# eps-v1-0.net
KiCad netlist of a schematic drawn in EAGLE
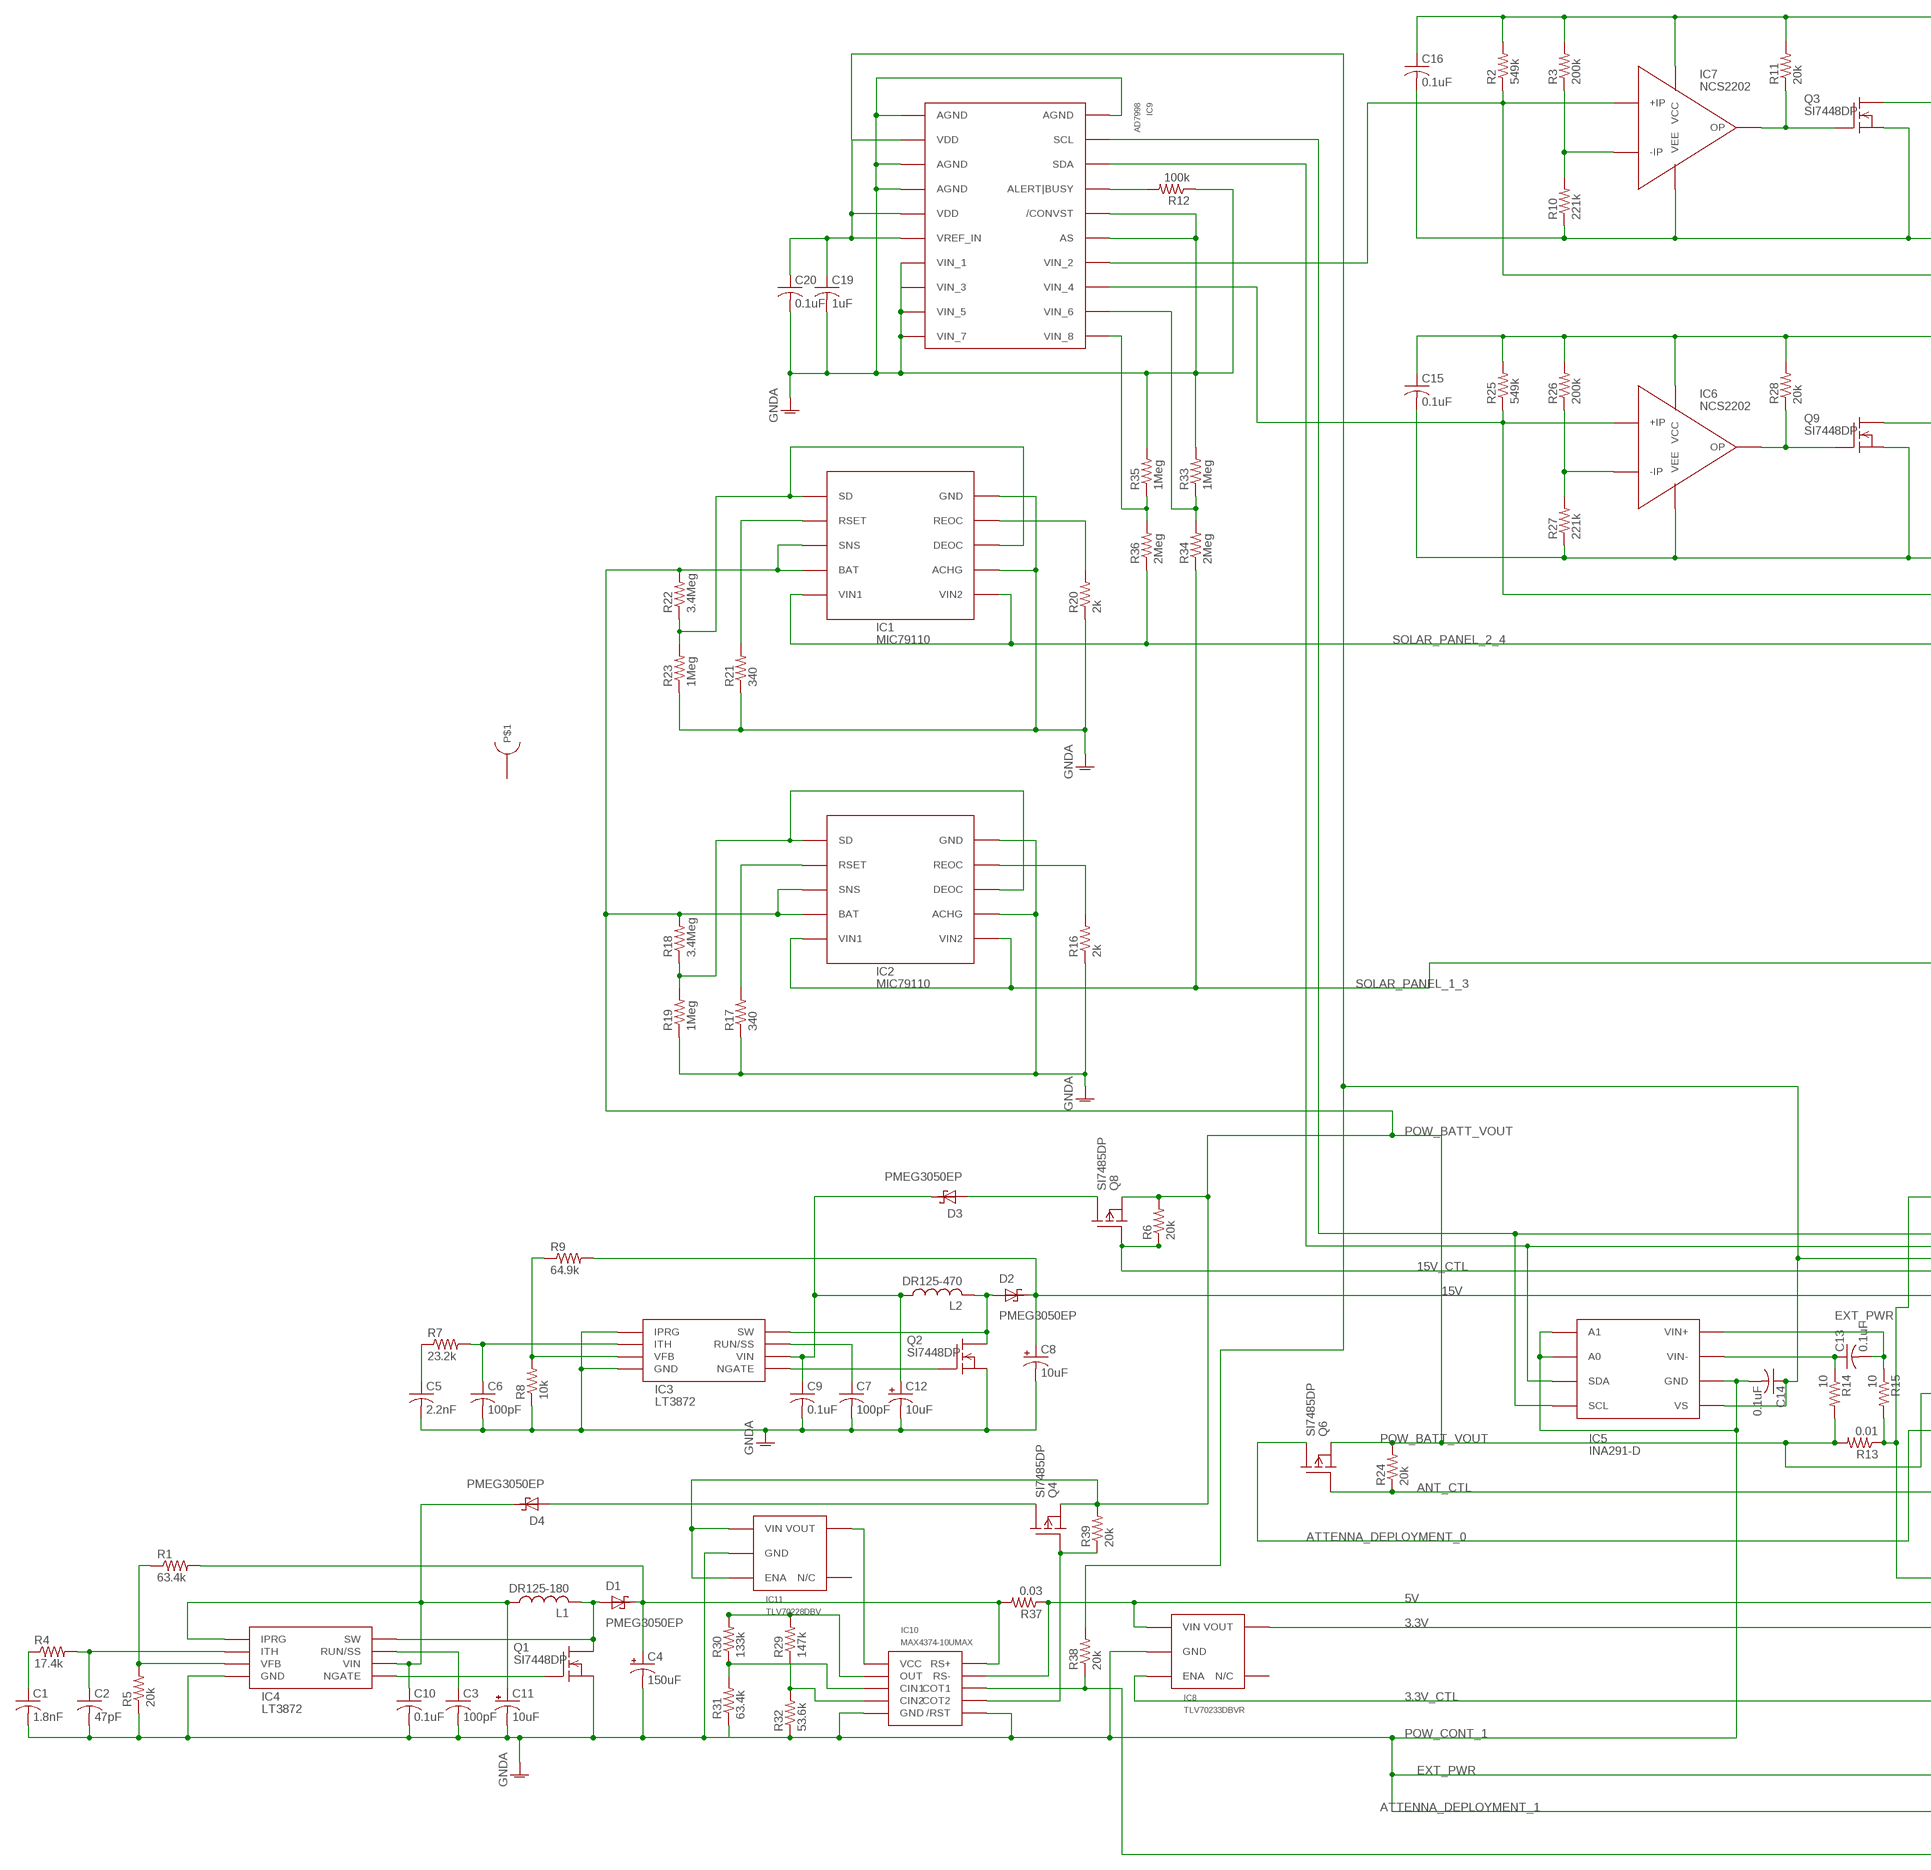
[diagram p0: schematic, sheet 1, part 1 of 2]
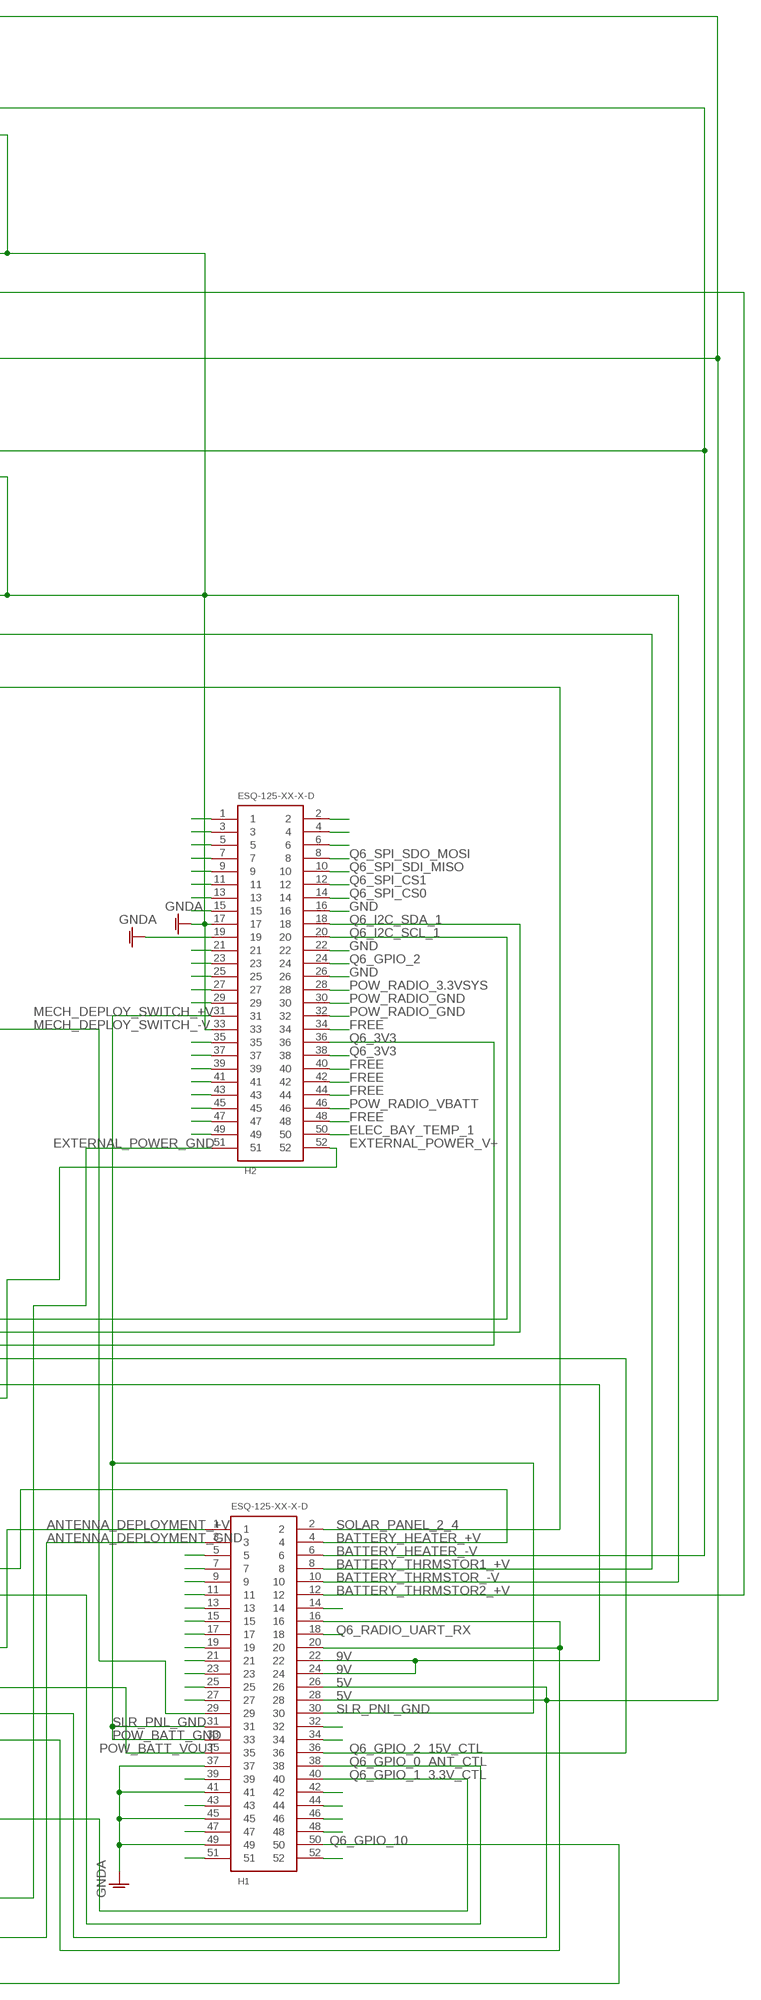
[diagram p1: schematic, sheet 1, part 2 of 2]

(export (version "E")
  (design (tool "Eeschema 10.0.6"))
  (components
    (comp (ref "C1")
      (value "1.8nF")
      (footprint "eagle-import:C0805")
      (libsource (lib "eagle-import") (part "C-USC0805"))
    )
    (comp (ref "C2")
      (value "47pF")
      (footprint "eagle-import:C0805")
      (libsource (lib "eagle-import") (part "C-USC0805"))
    )
    (comp (ref "C3")
      (value "100pF")
      (footprint "eagle-import:C0805")
      (libsource (lib "eagle-import") (part "C-USC0805"))
    )
    (comp (ref "C4")
      (value "150uF")
      (footprint "eagle-import:D_7343-31R")
      (libsource (lib "eagle-import") (part "CPOL-USD/7343-31R"))
    )
    (comp (ref "C5")
      (value "2.2nF")
      (footprint "eagle-import:C0805")
      (libsource (lib "eagle-import") (part "C-USC0805"))
    )
    (comp (ref "C6")
      (value "100pF")
      (footprint "eagle-import:C0805")
      (libsource (lib "eagle-import") (part "C-USC0805"))
    )
    (comp (ref "C7")
      (value "100pF")
      (footprint "eagle-import:C0805")
      (libsource (lib "eagle-import") (part "C-USC0805"))
    )
    (comp (ref "C8")
      (value "10uF")
      (footprint "eagle-import:D_7343-31R")
      (libsource (lib "eagle-import") (part "CPOL-USD/7343-31R"))
    )
    (comp (ref "C9")
      (value "0.1uF")
      (footprint "eagle-import:C0805")
      (libsource (lib "eagle-import") (part "C-USC0805"))
    )
    (comp (ref "C10")
      (value "0.1uF")
      (footprint "eagle-import:C0805")
      (libsource (lib "eagle-import") (part "C-USC0805"))
    )
    (comp (ref "C11")
      (value "10uF")
      (footprint "eagle-import:D_7343-31R")
      (libsource (lib "eagle-import") (part "CPOL-USD/7343-31R"))
    )
    (comp (ref "C12")
      (value "10uF")
      (footprint "eagle-import:D_7343-31R")
      (libsource (lib "eagle-import") (part "CPOL-USD/7343-31R"))
    )
    (comp (ref "C13")
      (value "0.1uF")
      (footprint "eagle-import:C0805")
      (libsource (lib "eagle-import") (part "C-USC0805"))
    )
    (comp (ref "C14")
      (value "0.1uF")
      (footprint "eagle-import:C0805")
      (libsource (lib "eagle-import") (part "C-USC0805"))
    )
    (comp (ref "C15")
      (value "0.1uF")
      (footprint "eagle-import:C0805")
      (libsource (lib "eagle-import") (part "C-USC0805"))
    )
    (comp (ref "C16")
      (value "0.1uF")
      (footprint "eagle-import:C0805")
      (libsource (lib "eagle-import") (part "C-USC0805"))
    )
    (comp (ref "C19")
      (value "1uF")
      (footprint "eagle-import:C0805")
      (libsource (lib "eagle-import") (part "C-USC0805"))
    )
    (comp (ref "C20")
      (value "0.1uF")
      (footprint "eagle-import:C0805")
      (libsource (lib "eagle-import") (part "C-USC0805"))
    )
    (comp (ref "D1")
      (value "PMEG3050EP")
      (footprint "eagle-import:SOD128")
      (libsource (lib "eagle-import") (part "PMEG3050EP"))
    )
    (comp (ref "D2")
      (value "PMEG3050EP")
      (footprint "eagle-import:SOD128")
      (libsource (lib "eagle-import") (part "PMEG3050EP"))
    )
    (comp (ref "D3")
      (value "PMEG3050EP")
      (footprint "eagle-import:SOD128")
      (libsource (lib "eagle-import") (part "PMEG3050EP"))
    )
    (comp (ref "D4")
      (value "PMEG3050EP")
      (footprint "eagle-import:SOD128")
      (libsource (lib "eagle-import") (part "PMEG3050EP"))
    )
    (comp (ref "H1")
      (value "ESQ-125-XX-X-D")
      (footprint "eagle-import:ESQ-125-XX-X-D")
      (libsource (lib "eagle-import") (part "ESQ-125-XX-X-D"))
    )
    (comp (ref "H2")
      (value "ESQ-125-XX-X-D")
      (footprint "eagle-import:ESQ-125-XX-X-D")
      (libsource (lib "eagle-import") (part "ESQ-125-XX-X-D"))
    )
    (comp (ref "IC1")
      (value "MIC79110")
      (footprint "eagle-import:MLF10-EP")
      (libsource (lib "eagle-import") (part "MIC79110"))
    )
    (comp (ref "IC2")
      (value "MIC79110")
      (footprint "eagle-import:MLF10-EP")
      (libsource (lib "eagle-import") (part "MIC79110"))
    )
    (comp (ref "IC3")
      (value "LT3872")
      (footprint "eagle-import:TSOT23-8")
      (libsource (lib "eagle-import") (part "LT3872"))
    )
    (comp (ref "IC4")
      (value "LT3872")
      (footprint "eagle-import:TSOT23-8")
      (libsource (lib "eagle-import") (part "LT3872"))
    )
    (comp (ref "IC5")
      (value "INA291-D")
      (footprint "eagle-import:SO08")
      (libsource (lib "eagle-import") (part "INA291-D"))
    )
    (comp (ref "IC6")
      (value "NCS2202")
      (footprint "eagle-import:SOT23-5")
      (libsource (lib "eagle-import") (part "NCS2202"))
    )
    (comp (ref "IC7")
      (value "NCS2202")
      (footprint "eagle-import:SOT23-5")
      (libsource (lib "eagle-import") (part "NCS2202"))
    )
    (comp (ref "IC8")
      (value "TLV70233DBVR")
      (footprint "eagle-import:SOT23-5")
      (libsource (lib "eagle-import") (part "TLV70233DBVR"))
    )
    (comp (ref "IC9")
      (value "AD7998")
      (footprint "eagle-import:TSSOP-20")
      (libsource (lib "eagle-import") (part "AD7998"))
    )
    (comp (ref "IC10")
      (value "MAX4374-10UMAX")
      (footprint "eagle-import:10UMAX")
      (libsource (lib "eagle-import") (part "MAX4374-10UMAX"))
    )
    (comp (ref "IC11")
      (value "TLV70228DBV")
      (footprint "eagle-import:SOT23-5")
      (libsource (lib "eagle-import") (part "TLV70228DBV"))
    )
    (comp (ref "L1")
      (value "DR125-180")
      (footprint "eagle-import:DR125")
      (libsource (lib "eagle-import") (part "DR125-180"))
    )
    (comp (ref "L2")
      (value "DR125-470")
      (footprint "eagle-import:DR125")
      (libsource (lib "eagle-import") (part "DR125-470"))
    )
    (comp (ref "Q1")
      (value "SI7448DP")
      (footprint "eagle-import:PPAK-SO08-EP")
      (libsource (lib "eagle-import") (part "SI7448DP"))
    )
    (comp (ref "Q2")
      (value "SI7448DP")
      (footprint "eagle-import:PPAK-SO08-EP")
      (libsource (lib "eagle-import") (part "SI7448DP"))
    )
    (comp (ref "Q3")
      (value "SI7448DP")
      (footprint "eagle-import:PPAK-SO08-EP")
      (libsource (lib "eagle-import") (part "SI7448DP"))
    )
    (comp (ref "Q4")
      (value "SI7485DP")
      (footprint "eagle-import:PPAK-SO08-EP")
      (libsource (lib "eagle-import") (part "SI7485DP"))
    )
    (comp (ref "Q6")
      (value "SI7485DP")
      (footprint "eagle-import:PPAK-SO08-EP")
      (libsource (lib "eagle-import") (part "SI7485DP"))
    )
    (comp (ref "Q8")
      (value "SI7485DP")
      (footprint "eagle-import:PPAK-SO08-EP")
      (libsource (lib "eagle-import") (part "SI7485DP"))
    )
    (comp (ref "Q9")
      (value "SI7448DP")
      (footprint "eagle-import:PPAK-SO08-EP")
      (libsource (lib "eagle-import") (part "SI7448DP"))
    )
    (comp (ref "R1")
      (value "63.4k")
      (footprint "eagle-import:M1206")
      (libsource (lib "eagle-import") (part "R-US_M1206"))
    )
    (comp (ref "R2")
      (value "549k")
      (footprint "eagle-import:M1206")
      (libsource (lib "eagle-import") (part "R-US_M1206"))
    )
    (comp (ref "R3")
      (value "200k")
      (footprint "eagle-import:M1206")
      (libsource (lib "eagle-import") (part "R-US_M1206"))
    )
    (comp (ref "R4")
      (value "17.4k")
      (footprint "eagle-import:M1206")
      (libsource (lib "eagle-import") (part "R-US_M1206"))
    )
    (comp (ref "R5")
      (value "20k")
      (footprint "eagle-import:M1206")
      (libsource (lib "eagle-import") (part "R-US_M1206"))
    )
    (comp (ref "R6")
      (value "20k")
      (footprint "eagle-import:M1206")
      (libsource (lib "eagle-import") (part "R-US_M1206"))
    )
    (comp (ref "R7")
      (value "23.2k")
      (footprint "eagle-import:M1206")
      (libsource (lib "eagle-import") (part "R-US_M1206"))
    )
    (comp (ref "R8")
      (value "10k")
      (footprint "eagle-import:M1206")
      (libsource (lib "eagle-import") (part "R-US_M1206"))
    )
    (comp (ref "R9")
      (value "64.9k")
      (footprint "eagle-import:M1206")
      (libsource (lib "eagle-import") (part "R-US_M1206"))
    )
    (comp (ref "R10")
      (value "221k")
      (footprint "eagle-import:M1206")
      (libsource (lib "eagle-import") (part "R-US_M1206"))
    )
    (comp (ref "R11")
      (value "20k")
      (footprint "eagle-import:M1206")
      (libsource (lib "eagle-import") (part "R-US_M1206"))
    )
    (comp (ref "R12")
      (value "100k")
      (footprint "eagle-import:M1206")
      (libsource (lib "eagle-import") (part "R-US_M1206"))
    )
    (comp (ref "R13")
      (value "0.01")
      (footprint "eagle-import:M1206")
      (libsource (lib "eagle-import") (part "R-US_M1206"))
    )
    (comp (ref "R14")
      (value "10")
      (footprint "eagle-import:M1206")
      (libsource (lib "eagle-import") (part "R-US_M1206"))
    )
    (comp (ref "R15")
      (value "10")
      (footprint "eagle-import:M1206")
      (libsource (lib "eagle-import") (part "R-US_M1206"))
    )
    (comp (ref "R16")
      (value "2k")
      (footprint "eagle-import:M1206")
      (libsource (lib "eagle-import") (part "R-US_M1206"))
    )
    (comp (ref "R17")
      (value "340")
      (footprint "eagle-import:M1206")
      (libsource (lib "eagle-import") (part "R-US_M1206"))
    )
    (comp (ref "R18")
      (value "3.4Meg")
      (footprint "eagle-import:M1206")
      (libsource (lib "eagle-import") (part "R-US_M1206"))
    )
    (comp (ref "R19")
      (value "1Meg")
      (footprint "eagle-import:M1206")
      (libsource (lib "eagle-import") (part "R-US_M1206"))
    )
    (comp (ref "R20")
      (value "2k")
      (footprint "eagle-import:M1206")
      (libsource (lib "eagle-import") (part "R-US_M1206"))
    )
    (comp (ref "R21")
      (value "340")
      (footprint "eagle-import:M1206")
      (libsource (lib "eagle-import") (part "R-US_M1206"))
    )
    (comp (ref "R22")
      (value "3.4Meg")
      (footprint "eagle-import:M1206")
      (libsource (lib "eagle-import") (part "R-US_M1206"))
    )
    (comp (ref "R23")
      (value "1Meg")
      (footprint "eagle-import:M1206")
      (libsource (lib "eagle-import") (part "R-US_M1206"))
    )
    (comp (ref "R24")
      (value "20k")
      (footprint "eagle-import:M1206")
      (libsource (lib "eagle-import") (part "R-US_M1206"))
    )
    (comp (ref "R25")
      (value "549k")
      (footprint "eagle-import:M1206")
      (libsource (lib "eagle-import") (part "R-US_M1206"))
    )
    (comp (ref "R26")
      (value "200k")
      (footprint "eagle-import:M1206")
      (libsource (lib "eagle-import") (part "R-US_M1206"))
    )
    (comp (ref "R27")
      (value "221k")
      (footprint "eagle-import:M1206")
      (libsource (lib "eagle-import") (part "R-US_M1206"))
    )
    (comp (ref "R28")
      (value "20k")
      (footprint "eagle-import:M1206")
      (libsource (lib "eagle-import") (part "R-US_M1206"))
    )
    (comp (ref "R29")
      (value "147k")
      (footprint "eagle-import:M1206")
      (libsource (lib "eagle-import") (part "R-US_M1206"))
    )
    (comp (ref "R30")
      (value "133k")
      (footprint "eagle-import:M1206")
      (libsource (lib "eagle-import") (part "R-US_M1206"))
    )
    (comp (ref "R31")
      (value "63.4k")
      (footprint "eagle-import:M1206")
      (libsource (lib "eagle-import") (part "R-US_M1206"))
    )
    (comp (ref "R32")
      (value "53.6k")
      (footprint "eagle-import:M1206")
      (libsource (lib "eagle-import") (part "R-US_M1206"))
    )
    (comp (ref "R33")
      (value "1Meg")
      (footprint "eagle-import:M1206")
      (libsource (lib "eagle-import") (part "R-US_M1206"))
    )
    (comp (ref "R34")
      (value "2Meg")
      (footprint "eagle-import:M1206")
      (libsource (lib "eagle-import") (part "R-US_M1206"))
    )
    (comp (ref "R35")
      (value "1Meg")
      (footprint "eagle-import:M1206")
      (libsource (lib "eagle-import") (part "R-US_M1206"))
    )
    (comp (ref "R36")
      (value "2Meg")
      (footprint "eagle-import:M1206")
      (libsource (lib "eagle-import") (part "R-US_M1206"))
    )
    (comp (ref "R37")
      (value "0.03")
      (footprint "eagle-import:M1206")
      (libsource (lib "eagle-import") (part "R-US_M1206"))
    )
    (comp (ref "R38")
      (value "20k")
      (footprint "eagle-import:M1206")
      (libsource (lib "eagle-import") (part "R-US_M1206"))
    )
    (comp (ref "R39")
      (value "20k")
      (footprint "eagle-import:M1206")
      (libsource (lib "eagle-import") (part "R-US_M1206"))
    )
    (comp (ref "U$1")
      (value "EPS_PCB_THRM_PAD")
      (footprint "eagle-import:EPS_PCB_THRM_PAD")
      (libsource (lib "eagle-import") (part "EPS_PCB_THRM_PAD"))
    )
  )
  (nets
    (net (code "1") (name "GNDA") (class "Default")
      (node (ref "C1") (pin "2") (pinfunction "2_2") (pintype "passive"))
      (node (ref "C10") (pin "2") (pinfunction "2_2") (pintype "passive"))
      (node (ref "C11") (pin "-") (pinfunction "-_-") (pintype "passive"))
      (node (ref "C12") (pin "-") (pinfunction "-_-") (pintype "passive"))
      (node (ref "C14") (pin "2") (pinfunction "2_2") (pintype "passive"))
      (node (ref "C15") (pin "2") (pinfunction "2_2") (pintype "passive"))
      (node (ref "C16") (pin "2") (pinfunction "2_2") (pintype "passive"))
      (node (ref "C19") (pin "2") (pinfunction "2_2") (pintype "passive"))
      (node (ref "C2") (pin "2") (pinfunction "2_2") (pintype "passive"))
      (node (ref "C20") (pin "2") (pinfunction "2_2") (pintype "passive"))
      (node (ref "C3") (pin "2") (pinfunction "2_2") (pintype "passive"))
      (node (ref "C4") (pin "-") (pinfunction "-_-") (pintype "passive"))
      (node (ref "C5") (pin "2") (pinfunction "2_2") (pintype "passive"))
      (node (ref "C6") (pin "2") (pinfunction "2_2") (pintype "passive"))
      (node (ref "C7") (pin "2") (pinfunction "2_2") (pintype "passive"))
      (node (ref "C8") (pin "-") (pinfunction "-_-") (pintype "passive"))
      (node (ref "C9") (pin "2") (pinfunction "2_2") (pintype "passive"))
      (node (ref "H1") (pin "10") (pinfunction "10_10") (pintype "bidirectional"))
      (node (ref "H1") (pin "3") (pinfunction "3_3") (pintype "bidirectional"))
      (node (ref "H1") (pin "37") (pinfunction "37_37") (pintype "bidirectional"))
      (node (ref "H1") (pin "41") (pinfunction "41_41") (pintype "bidirectional"))
      (node (ref "H1") (pin "45") (pinfunction "45_45") (pintype "bidirectional"))
      (node (ref "H1") (pin "49") (pinfunction "49_49") (pintype "bidirectional"))
      (node (ref "H2") (pin "17") (pinfunction "17_17") (pintype "bidirectional"))
      (node (ref "H2") (pin "19") (pinfunction "19_19") (pintype "bidirectional"))
      (node (ref "H2") (pin "33") (pinfunction "33_33") (pintype "bidirectional"))
      (node (ref "H2") (pin "51") (pinfunction "51_51") (pintype "bidirectional"))
      (node (ref "IC1") (pin "P$10") (pinfunction "GND_P$10") (pintype "bidirectional"))
      (node (ref "IC1") (pin "P$7") (pinfunction "ACHG_P$7") (pintype "bidirectional"))
      (node (ref "IC10") (pin "P$5") (pinfunction "GND_P$5") (pintype "bidirectional"))
      (node (ref "IC10") (pin "P$6") (pinfunction "/RST_P$6") (pintype "bidirectional"))
      (node (ref "IC11") (pin "2") (pinfunction "GND_2") (pintype "bidirectional"))
      (node (ref "IC2") (pin "P$10") (pinfunction "GND_P$10") (pintype "bidirectional"))
      (node (ref "IC2") (pin "P$7") (pinfunction "ACHG_P$7") (pintype "bidirectional"))
      (node (ref "IC3") (pin "P$1") (pinfunction "IPRG_P$1") (pintype "bidirectional"))
      (node (ref "IC3") (pin "P$4") (pinfunction "GND_P$4") (pintype "bidirectional"))
      (node (ref "IC4") (pin "P$4") (pinfunction "GND_P$4") (pintype "bidirectional"))
      (node (ref "IC5") (pin "1") (pinfunction "A1_1") (pintype "bidirectional"))
      (node (ref "IC5") (pin "2") (pinfunction "A0_2") (pintype "bidirectional"))
      (node (ref "IC5") (pin "6") (pinfunction "GND_6") (pintype "bidirectional"))
      (node (ref "IC6") (pin "5") (pinfunction "VEE_5") (pintype "bidirectional"))
      (node (ref "IC7") (pin "5") (pinfunction "VEE_5") (pintype "bidirectional"))
      (node (ref "IC8") (pin "2") (pinfunction "GND_2") (pintype "bidirectional"))
      (node (ref "IC9") (pin "P$1") (pinfunction "AGND_P$1") (pintype "bidirectional"))
      (node (ref "IC9") (pin "P$10") (pinfunction "VIN_7_P$10") (pintype "bidirectional"))
      (node (ref "IC9") (pin "P$15") (pinfunction "AS_P$15") (pintype "bidirectional"))
      (node (ref "IC9") (pin "P$16") (pinfunction "/CONVST_P$16") (pintype "bidirectional"))
      (node (ref "IC9") (pin "P$20") (pinfunction "AGND_P$20") (pintype "bidirectional"))
      (node (ref "IC9") (pin "P$3") (pinfunction "AGND_P$3") (pintype "bidirectional"))
      (node (ref "IC9") (pin "P$4") (pinfunction "AGND_P$4") (pintype "bidirectional"))
      (node (ref "IC9") (pin "P$7") (pinfunction "VIN_1_P$7") (pintype "bidirectional"))
      (node (ref "IC9") (pin "P$8") (pinfunction "VIN_3_P$8") (pintype "bidirectional"))
      (node (ref "IC9") (pin "P$9") (pinfunction "VIN_5_P$9") (pintype "bidirectional"))
      (node (ref "Q1") (pin "P$1-S") (pinfunction "S_P$1-S") (pintype "passive"))
      (node (ref "Q1") (pin "P$2-S") (pinfunction "S_P$2-S") (pintype "passive"))
      (node (ref "Q1") (pin "P$3-S") (pinfunction "S_P$3-S") (pintype "passive"))
      (node (ref "Q2") (pin "P$1-S") (pinfunction "S_P$1-S") (pintype "passive"))
      (node (ref "Q2") (pin "P$2-S") (pinfunction "S_P$2-S") (pintype "passive"))
      (node (ref "Q2") (pin "P$3-S") (pinfunction "S_P$3-S") (pintype "passive"))
      (node (ref "Q3") (pin "P$1-S") (pinfunction "S_P$1-S") (pintype "passive"))
      (node (ref "Q3") (pin "P$2-S") (pinfunction "S_P$2-S") (pintype "passive"))
      (node (ref "Q3") (pin "P$3-S") (pinfunction "S_P$3-S") (pintype "passive"))
      (node (ref "Q9") (pin "P$1-S") (pinfunction "S_P$1-S") (pintype "passive"))
      (node (ref "Q9") (pin "P$2-S") (pinfunction "S_P$2-S") (pintype "passive"))
      (node (ref "Q9") (pin "P$3-S") (pinfunction "S_P$3-S") (pintype "passive"))
      (node (ref "R10") (pin "1") (pinfunction "1_1") (pintype "passive"))
      (node (ref "R12") (pin "1") (pinfunction "1_1") (pintype "passive"))
      (node (ref "R16") (pin "1") (pinfunction "1_1") (pintype "passive"))
      (node (ref "R17") (pin "1") (pinfunction "1_1") (pintype "passive"))
      (node (ref "R19") (pin "1") (pinfunction "1_1") (pintype "passive"))
      (node (ref "R20") (pin "1") (pinfunction "1_1") (pintype "passive"))
      (node (ref "R21") (pin "1") (pinfunction "1_1") (pintype "passive"))
      (node (ref "R23") (pin "1") (pinfunction "1_1") (pintype "passive"))
      (node (ref "R27") (pin "1") (pinfunction "1_1") (pintype "passive"))
      (node (ref "R31") (pin "1") (pinfunction "1_1") (pintype "passive"))
      (node (ref "R32") (pin "1") (pinfunction "1_1") (pintype "passive"))
      (node (ref "R33") (pin "2") (pinfunction "2_2") (pintype "passive"))
      (node (ref "R35") (pin "2") (pinfunction "2_2") (pintype "passive"))
      (node (ref "R5") (pin "1") (pinfunction "1_1") (pintype "passive"))
      (node (ref "R8") (pin "1") (pinfunction "1_1") (pintype "passive"))
    )
    (net (code "2") (name "Net-(C1-Pad1)") (class "Default")
      (node (ref "C1") (pin "1") (pinfunction "1_1") (pintype "passive"))
      (node (ref "R4") (pin "1") (pinfunction "1_1") (pintype "passive"))
    )
    (net (code "3") (name "Net-(C5-Pad1)") (class "Default")
      (node (ref "C5") (pin "1") (pinfunction "1_1") (pintype "passive"))
      (node (ref "R7") (pin "1") (pinfunction "1_1") (pintype "passive"))
    )
    (net (code "4") (name "Net-(C8-Pad+)") (class "Default")
      (node (ref "C8") (pin "+") (pinfunction "+_+") (pintype "passive"))
      (node (ref "D2") (pin "P$1-CATHODE") (pinfunction "P$1-CATHODE_P$1-CATHODE") (pintype "bidirectional"))
      (node (ref "H1") (pin "22") (pinfunction "22_22") (pintype "bidirectional"))
      (node (ref "H1") (pin "24") (pinfunction "24_24") (pintype "bidirectional"))
      (node (ref "R9") (pin "2") (pinfunction "2_2") (pintype "passive"))
    )
    (net (code "5") (name "Net-(D3-PadP$2-ANODE)") (class "Default")
      (node (ref "D3") (pin "P$2-ANODE") (pinfunction "P$2-ANODE_P$2-ANODE") (pintype "bidirectional"))
      (node (ref "Q8") (pin "P$10-D") (pinfunction "D_P$10-D") (pintype "passive"))
      (node (ref "Q8") (pin "P$11-D") (pinfunction "D_P$11-D") (pintype "passive"))
      (node (ref "Q8") (pin "P$5-D") (pinfunction "D_P$5-D") (pintype "passive"))
      (node (ref "Q8") (pin "P$6-D") (pinfunction "D_P$6-D") (pintype "passive"))
      (node (ref "Q8") (pin "P$7-D") (pinfunction "D_P$7-D") (pintype "passive"))
      (node (ref "Q8") (pin "P$8-D") (pinfunction "D_P$8-D") (pintype "passive"))
      (node (ref "Q8") (pin "P$9-D") (pinfunction "D_P$9-D") (pintype "passive"))
    )
    (net (code "6") (name "Net-(D4-PadP$2-ANODE)") (class "Default")
      (node (ref "D4") (pin "P$2-ANODE") (pinfunction "P$2-ANODE_P$2-ANODE") (pintype "bidirectional"))
      (node (ref "Q4") (pin "P$10-D") (pinfunction "D_P$10-D") (pintype "passive"))
      (node (ref "Q4") (pin "P$11-D") (pinfunction "D_P$11-D") (pintype "passive"))
      (node (ref "Q4") (pin "P$5-D") (pinfunction "D_P$5-D") (pintype "passive"))
      (node (ref "Q4") (pin "P$6-D") (pinfunction "D_P$6-D") (pintype "passive"))
      (node (ref "Q4") (pin "P$7-D") (pinfunction "D_P$7-D") (pintype "passive"))
      (node (ref "Q4") (pin "P$8-D") (pinfunction "D_P$8-D") (pintype "passive"))
      (node (ref "Q4") (pin "P$9-D") (pinfunction "D_P$9-D") (pintype "passive"))
    )
    (net (code "7") (name "Net-(H1-Pad1)") (class "Default")
      (node (ref "H1") (pin "1") (pinfunction "1_1") (pintype "bidirectional"))
      (node (ref "Q6") (pin "P$10-D") (pinfunction "D_P$10-D") (pintype "passive"))
      (node (ref "Q6") (pin "P$11-D") (pinfunction "D_P$11-D") (pintype "passive"))
      (node (ref "Q6") (pin "P$5-D") (pinfunction "D_P$5-D") (pintype "passive"))
      (node (ref "Q6") (pin "P$6-D") (pinfunction "D_P$6-D") (pintype "passive"))
      (node (ref "Q6") (pin "P$7-D") (pinfunction "D_P$7-D") (pintype "passive"))
      (node (ref "Q6") (pin "P$8-D") (pinfunction "D_P$8-D") (pintype "passive"))
      (node (ref "Q6") (pin "P$9-D") (pinfunction "D_P$9-D") (pintype "passive"))
    )
    (net (code "8") (name "Net-(H1-Pad6)") (class "Default")
      (node (ref "H1") (pin "6") (pinfunction "6_6") (pintype "bidirectional"))
      (node (ref "Q3") (pin "P$10-D") (pinfunction "D_P$10-D") (pintype "passive"))
      (node (ref "Q3") (pin "P$11-D") (pinfunction "D_P$11-D") (pintype "passive"))
      (node (ref "Q3") (pin "P$5-D") (pinfunction "D_P$5-D") (pintype "passive"))
      (node (ref "Q3") (pin "P$6-D") (pinfunction "D_P$6-D") (pintype "passive"))
      (node (ref "Q3") (pin "P$7-D") (pinfunction "D_P$7-D") (pintype "passive"))
      (node (ref "Q3") (pin "P$8-D") (pinfunction "D_P$8-D") (pintype "passive"))
      (node (ref "Q3") (pin "P$9-D") (pinfunction "D_P$9-D") (pintype "passive"))
      (node (ref "Q9") (pin "P$10-D") (pinfunction "D_P$10-D") (pintype "passive"))
      (node (ref "Q9") (pin "P$11-D") (pinfunction "D_P$11-D") (pintype "passive"))
      (node (ref "Q9") (pin "P$5-D") (pinfunction "D_P$5-D") (pintype "passive"))
      (node (ref "Q9") (pin "P$6-D") (pinfunction "D_P$6-D") (pintype "passive"))
      (node (ref "Q9") (pin "P$7-D") (pinfunction "D_P$7-D") (pintype "passive"))
      (node (ref "Q9") (pin "P$8-D") (pinfunction "D_P$8-D") (pintype "passive"))
      (node (ref "Q9") (pin "P$9-D") (pinfunction "D_P$9-D") (pintype "passive"))
    )
    (net (code "9") (name "Net-(H1-Pad30)") (class "Default")
      (node (ref "H1") (pin "30") (pinfunction "30_30") (pintype "bidirectional"))
      (node (ref "H1") (pin "31") (pinfunction "31_31") (pintype "bidirectional"))
      (node (ref "H1") (pin "33") (pinfunction "33_33") (pintype "bidirectional"))
      (node (ref "H2") (pin "31") (pinfunction "31_31") (pintype "bidirectional"))
    )
    (net (code "10") (name "Net-(H1-Pad35)") (class "Default")
      (node (ref "H1") (pin "35") (pinfunction "35_35") (pintype "bidirectional"))
      (node (ref "H2") (pin "52") (pinfunction "52_52") (pintype "bidirectional"))
      (node (ref "R13") (pin "1") (pinfunction "1_1") (pintype "passive"))
      (node (ref "R15") (pin "2") (pinfunction "2_2") (pintype "passive"))
    )
    (net (code "11") (name "Net-(IC1-BAT)") (class "Default")
      (node (ref "H1") (pin "4") (pinfunction "4_4") (pintype "bidirectional"))
      (node (ref "IC1") (pin "P$3") (pinfunction "SNS_P$3") (pintype "bidirectional"))
      (node (ref "IC1") (pin "P$4") (pinfunction "BAT_P$4") (pintype "bidirectional"))
      (node (ref "IC11") (pin "1") (pinfunction "VIN_1") (pintype "bidirectional"))
      (node (ref "IC11") (pin "3") (pinfunction "ENA_3") (pintype "bidirectional"))
      (node (ref "IC2") (pin "P$3") (pinfunction "SNS_P$3") (pintype "bidirectional"))
      (node (ref "IC2") (pin "P$4") (pinfunction "BAT_P$4") (pintype "bidirectional"))
      (node (ref "Q4") (pin "P$1-S") (pinfunction "S_P$1-S") (pintype "passive"))
      (node (ref "Q4") (pin "P$2-S") (pinfunction "S_P$2-S") (pintype "passive"))
      (node (ref "Q4") (pin "P$3-S") (pinfunction "S_P$3-S") (pintype "passive"))
      (node (ref "Q6") (pin "P$1-S") (pinfunction "S_P$1-S") (pintype "passive"))
      (node (ref "Q6") (pin "P$2-S") (pinfunction "S_P$2-S") (pintype "passive"))
      (node (ref "Q6") (pin "P$3-S") (pinfunction "S_P$3-S") (pintype "passive"))
      (node (ref "Q8") (pin "P$1-S") (pinfunction "S_P$1-S") (pintype "passive"))
      (node (ref "Q8") (pin "P$2-S") (pinfunction "S_P$2-S") (pintype "passive"))
      (node (ref "Q8") (pin "P$3-S") (pinfunction "S_P$3-S") (pintype "passive"))
      (node (ref "R13") (pin "2") (pinfunction "2_2") (pintype "passive"))
      (node (ref "R14") (pin "2") (pinfunction "2_2") (pintype "passive"))
      (node (ref "R18") (pin "2") (pinfunction "2_2") (pintype "passive"))
      (node (ref "R22") (pin "2") (pinfunction "2_2") (pintype "passive"))
      (node (ref "R24") (pin "2") (pinfunction "2_2") (pintype "passive"))
      (node (ref "R39") (pin "2") (pinfunction "2_2") (pintype "passive"))
      (node (ref "R6") (pin "2") (pinfunction "2_2") (pintype "passive"))
    )
    (net (code "12") (name "Net-(IC1-DEOC)") (class "Default")
      (node (ref "IC1") (pin "P$1") (pinfunction "SD_P$1") (pintype "bidirectional"))
      (node (ref "IC1") (pin "P$8") (pinfunction "DEOC_P$8") (pintype "bidirectional"))
      (node (ref "R22") (pin "1") (pinfunction "1_1") (pintype "passive"))
      (node (ref "R23") (pin "2") (pinfunction "2_2") (pintype "passive"))
    )
    (net (code "13") (name "Net-(IC1-REOC)") (class "Default")
      (node (ref "IC1") (pin "P$9") (pinfunction "REOC_P$9") (pintype "bidirectional"))
      (node (ref "R20") (pin "2") (pinfunction "2_2") (pintype "passive"))
    )
    (net (code "14") (name "Net-(IC1-RSET)") (class "Default")
      (node (ref "IC1") (pin "P$2") (pinfunction "RSET_P$2") (pintype "bidirectional"))
      (node (ref "R21") (pin "2") (pinfunction "2_2") (pintype "passive"))
    )
    (net (code "15") (name "Net-(IC1-VIN1)") (class "Default")
      (node (ref "H1") (pin "2") (pinfunction "2_2") (pintype "bidirectional"))
      (node (ref "IC1") (pin "P$5") (pinfunction "VIN1_P$5") (pintype "bidirectional"))
      (node (ref "IC1") (pin "P$6") (pinfunction "VIN2_P$6") (pintype "bidirectional"))
      (node (ref "R36") (pin "1") (pinfunction "1_1") (pintype "passive"))
    )
    (net (code "16") (name "Net-(IC2-DEOC)") (class "Default")
      (node (ref "IC2") (pin "P$1") (pinfunction "SD_P$1") (pintype "bidirectional"))
      (node (ref "IC2") (pin "P$8") (pinfunction "DEOC_P$8") (pintype "bidirectional"))
      (node (ref "R18") (pin "1") (pinfunction "1_1") (pintype "passive"))
      (node (ref "R19") (pin "2") (pinfunction "2_2") (pintype "passive"))
    )
    (net (code "17") (name "Net-(IC2-REOC)") (class "Default")
      (node (ref "IC2") (pin "P$9") (pinfunction "REOC_P$9") (pintype "bidirectional"))
      (node (ref "R16") (pin "2") (pinfunction "2_2") (pintype "passive"))
    )
    (net (code "18") (name "Net-(IC2-RSET)") (class "Default")
      (node (ref "IC2") (pin "P$2") (pinfunction "RSET_P$2") (pintype "bidirectional"))
      (node (ref "R17") (pin "2") (pinfunction "2_2") (pintype "passive"))
    )
    (net (code "19") (name "Net-(IC2-VIN1)") (class "Default")
      (node (ref "H1") (pin "29") (pinfunction "29_29") (pintype "bidirectional"))
      (node (ref "IC2") (pin "P$5") (pinfunction "VIN1_P$5") (pintype "bidirectional"))
      (node (ref "IC2") (pin "P$6") (pinfunction "VIN2_P$6") (pintype "bidirectional"))
      (node (ref "R34") (pin "1") (pinfunction "1_1") (pintype "passive"))
    )
    (net (code "20") (name "Net-(IC3-ITH)") (class "Default")
      (node (ref "C6") (pin "1") (pinfunction "1_1") (pintype "passive"))
      (node (ref "IC3") (pin "P$2") (pinfunction "ITH_P$2") (pintype "bidirectional"))
      (node (ref "R7") (pin "2") (pinfunction "2_2") (pintype "passive"))
    )
    (net (code "21") (name "Net-(IC3-NGATE)") (class "Default")
      (node (ref "IC3") (pin "P$5") (pinfunction "NGATE_P$5") (pintype "bidirectional"))
      (node (ref "Q2") (pin "P$4-G") (pinfunction "G_P$4-G") (pintype "passive"))
    )
    (net (code "22") (name "Net-(IC3-RUN{slash}SS)") (class "Default")
      (node (ref "C7") (pin "1") (pinfunction "1_1") (pintype "passive"))
      (node (ref "IC3") (pin "P$7") (pinfunction "RUN/SS_P$7") (pintype "bidirectional"))
    )
    (net (code "23") (name "Net-(IC3-SW)") (class "Default")
      (node (ref "D2") (pin "P$2-ANODE") (pinfunction "P$2-ANODE_P$2-ANODE") (pintype "bidirectional"))
      (node (ref "IC3") (pin "P$8") (pinfunction "SW_P$8") (pintype "bidirectional"))
      (node (ref "L2") (pin "P$2") (pinfunction "2_P$2") (pintype "passive"))
      (node (ref "Q2") (pin "P$10-D") (pinfunction "D_P$10-D") (pintype "passive"))
      (node (ref "Q2") (pin "P$11-D") (pinfunction "D_P$11-D") (pintype "passive"))
      (node (ref "Q2") (pin "P$5-D") (pinfunction "D_P$5-D") (pintype "passive"))
      (node (ref "Q2") (pin "P$6-D") (pinfunction "D_P$6-D") (pintype "passive"))
      (node (ref "Q2") (pin "P$7-D") (pinfunction "D_P$7-D") (pintype "passive"))
      (node (ref "Q2") (pin "P$8-D") (pinfunction "D_P$8-D") (pintype "passive"))
      (node (ref "Q2") (pin "P$9-D") (pinfunction "D_P$9-D") (pintype "passive"))
    )
    (net (code "24") (name "Net-(IC3-VFB)") (class "Default")
      (node (ref "IC3") (pin "P$3") (pinfunction "VFB_P$3") (pintype "bidirectional"))
      (node (ref "R8") (pin "2") (pinfunction "2_2") (pintype "passive"))
      (node (ref "R9") (pin "1") (pinfunction "1_1") (pintype "passive"))
    )
    (net (code "25") (name "Net-(IC3-VIN)") (class "Default")
      (node (ref "C12") (pin "+") (pinfunction "+_+") (pintype "passive"))
      (node (ref "C9") (pin "1") (pinfunction "1_1") (pintype "passive"))
      (node (ref "D3") (pin "P$1-CATHODE") (pinfunction "P$1-CATHODE_P$1-CATHODE") (pintype "bidirectional"))
      (node (ref "IC3") (pin "P$6") (pinfunction "VIN_P$6") (pintype "bidirectional"))
      (node (ref "L2") (pin "P$1") (pinfunction "1_P$1") (pintype "passive"))
    )
    (net (code "26") (name "Net-(IC4-IPRG)") (class "Default")
      (node (ref "C10") (pin "1") (pinfunction "1_1") (pintype "passive"))
      (node (ref "C11") (pin "+") (pinfunction "+_+") (pintype "passive"))
      (node (ref "D4") (pin "P$1-CATHODE") (pinfunction "P$1-CATHODE_P$1-CATHODE") (pintype "bidirectional"))
      (node (ref "IC4") (pin "P$1") (pinfunction "IPRG_P$1") (pintype "bidirectional"))
      (node (ref "IC4") (pin "P$6") (pinfunction "VIN_P$6") (pintype "bidirectional"))
      (node (ref "L1") (pin "P$1") (pinfunction "1_P$1") (pintype "passive"))
    )
    (net (code "27") (name "Net-(IC4-ITH)") (class "Default")
      (node (ref "C2") (pin "1") (pinfunction "1_1") (pintype "passive"))
      (node (ref "IC4") (pin "P$2") (pinfunction "ITH_P$2") (pintype "bidirectional"))
      (node (ref "R4") (pin "2") (pinfunction "2_2") (pintype "passive"))
    )
    (net (code "28") (name "Net-(IC4-NGATE)") (class "Default")
      (node (ref "IC4") (pin "P$5") (pinfunction "NGATE_P$5") (pintype "bidirectional"))
      (node (ref "Q1") (pin "P$4-G") (pinfunction "G_P$4-G") (pintype "passive"))
    )
    (net (code "29") (name "Net-(IC4-RUN{slash}SS)") (class "Default")
      (node (ref "C3") (pin "1") (pinfunction "1_1") (pintype "passive"))
      (node (ref "IC4") (pin "P$7") (pinfunction "RUN/SS_P$7") (pintype "bidirectional"))
    )
    (net (code "30") (name "Net-(IC4-SW)") (class "Default")
      (node (ref "D1") (pin "P$2-ANODE") (pinfunction "P$2-ANODE_P$2-ANODE") (pintype "bidirectional"))
      (node (ref "IC4") (pin "P$8") (pinfunction "SW_P$8") (pintype "bidirectional"))
      (node (ref "L1") (pin "P$2") (pinfunction "2_P$2") (pintype "passive"))
      (node (ref "Q1") (pin "P$10-D") (pinfunction "D_P$10-D") (pintype "passive"))
      (node (ref "Q1") (pin "P$11-D") (pinfunction "D_P$11-D") (pintype "passive"))
      (node (ref "Q1") (pin "P$5-D") (pinfunction "D_P$5-D") (pintype "passive"))
      (node (ref "Q1") (pin "P$6-D") (pinfunction "D_P$6-D") (pintype "passive"))
      (node (ref "Q1") (pin "P$7-D") (pinfunction "D_P$7-D") (pintype "passive"))
      (node (ref "Q1") (pin "P$8-D") (pinfunction "D_P$8-D") (pintype "passive"))
      (node (ref "Q1") (pin "P$9-D") (pinfunction "D_P$9-D") (pintype "passive"))
    )
    (net (code "31") (name "Net-(IC4-VFB)") (class "Default")
      (node (ref "IC4") (pin "P$3") (pinfunction "VFB_P$3") (pintype "bidirectional"))
      (node (ref "R1") (pin "1") (pinfunction "1_1") (pintype "passive"))
      (node (ref "R5") (pin "2") (pinfunction "2_2") (pintype "passive"))
    )
    (net (code "32") (name "Net-(IC5-SCL)") (class "Default")
      (node (ref "H2") (pin "20") (pinfunction "20_20") (pintype "bidirectional"))
      (node (ref "IC5") (pin "4") (pinfunction "SCL_4") (pintype "bidirectional"))
      (node (ref "IC9") (pin "P$19") (pinfunction "SCL_P$19") (pintype "bidirectional"))
    )
    (net (code "33") (name "Net-(IC5-SDA)") (class "Default")
      (node (ref "H2") (pin "18") (pinfunction "18_18") (pintype "bidirectional"))
      (node (ref "IC5") (pin "3") (pinfunction "SDA_3") (pintype "bidirectional"))
      (node (ref "IC9") (pin "P$18") (pinfunction "SDA_P$18") (pintype "bidirectional"))
    )
    (net (code "34") (name "Net-(IC5-VIN+)") (class "Default")
      (node (ref "C13") (pin "2") (pinfunction "2_2") (pintype "passive"))
      (node (ref "IC5") (pin "8") (pinfunction "VIN+_8") (pintype "bidirectional"))
      (node (ref "R15") (pin "1") (pinfunction "1_1") (pintype "passive"))
    )
    (net (code "35") (name "Net-(IC5-VIN-)") (class "Default")
      (node (ref "C13") (pin "1") (pinfunction "1_1") (pintype "passive"))
      (node (ref "IC5") (pin "7") (pinfunction "VIN-_7") (pintype "bidirectional"))
      (node (ref "R14") (pin "1") (pinfunction "1_1") (pintype "passive"))
    )
    (net (code "36") (name "Net-(IC5-VS)") (class "Default")
      (node (ref "C14") (pin "1") (pinfunction "1_1") (pintype "passive"))
      (node (ref "C19") (pin "1") (pinfunction "1_1") (pintype "passive"))
      (node (ref "C20") (pin "1") (pinfunction "1_1") (pintype "passive"))
      (node (ref "H2") (pin "36") (pinfunction "36_36") (pintype "bidirectional"))
      (node (ref "IC5") (pin "5") (pinfunction "VS_5") (pintype "bidirectional"))
      (node (ref "IC9") (pin "P$2") (pinfunction "VDD_P$2") (pintype "bidirectional"))
      (node (ref "IC9") (pin "P$5") (pinfunction "VDD_P$5") (pintype "bidirectional"))
      (node (ref "IC9") (pin "P$6") (pinfunction "VREF_IN_P$6") (pintype "bidirectional"))
      (node (ref "R38") (pin "2") (pinfunction "2_2") (pintype "passive"))
    )
    (net (code "37") (name "Net-(IC6-+IP)") (class "Default")
      (node (ref "H1") (pin "8") (pinfunction "8_8") (pintype "bidirectional"))
      (node (ref "IC6") (pin "3") (pinfunction "+IP_3") (pintype "bidirectional"))
      (node (ref "IC9") (pin "P$13") (pinfunction "VIN_4_P$13") (pintype "bidirectional"))
      (node (ref "R25") (pin "1") (pinfunction "1_1") (pintype "passive"))
    )
    (net (code "38") (name "Net-(IC6--IP)") (class "Default")
      (node (ref "IC6") (pin "4") (pinfunction "-IP_4") (pintype "bidirectional"))
      (node (ref "R26") (pin "1") (pinfunction "1_1") (pintype "passive"))
      (node (ref "R27") (pin "2") (pinfunction "2_2") (pintype "passive"))
    )
    (net (code "39") (name "Net-(IC6-OP)") (class "Default")
      (node (ref "IC6") (pin "1") (pinfunction "OP_1") (pintype "bidirectional"))
      (node (ref "Q9") (pin "P$4-G") (pinfunction "G_P$4-G") (pintype "passive"))
      (node (ref "R28") (pin "1") (pinfunction "1_1") (pintype "passive"))
    )
    (net (code "40") (name "Net-(IC7-+IP)") (class "Default")
      (node (ref "H1") (pin "12") (pinfunction "12_12") (pintype "bidirectional"))
      (node (ref "IC7") (pin "3") (pinfunction "+IP_3") (pintype "bidirectional"))
      (node (ref "IC9") (pin "P$14") (pinfunction "VIN_2_P$14") (pintype "bidirectional"))
      (node (ref "R2") (pin "1") (pinfunction "1_1") (pintype "passive"))
    )
    (net (code "41") (name "Net-(IC7--IP)") (class "Default")
      (node (ref "IC7") (pin "4") (pinfunction "-IP_4") (pintype "bidirectional"))
      (node (ref "R10") (pin "2") (pinfunction "2_2") (pintype "passive"))
      (node (ref "R3") (pin "1") (pinfunction "1_1") (pintype "passive"))
    )
    (net (code "42") (name "Net-(IC7-OP)") (class "Default")
      (node (ref "IC7") (pin "1") (pinfunction "OP_1") (pintype "bidirectional"))
      (node (ref "Q3") (pin "P$4-G") (pinfunction "G_P$4-G") (pintype "passive"))
      (node (ref "R11") (pin "1") (pinfunction "1_1") (pintype "passive"))
    )
    (net (code "43") (name "Net-(IC8-ENA)") (class "Default")
      (node (ref "H1") (pin "40") (pinfunction "40_40") (pintype "bidirectional"))
      (node (ref "IC8") (pin "3") (pinfunction "ENA_3") (pintype "bidirectional"))
    )
    (net (code "44") (name "Net-(IC8-VOUT)") (class "Default")
      (node (ref "H1") (pin "16") (pinfunction "16_16") (pintype "bidirectional"))
      (node (ref "H1") (pin "20") (pinfunction "20_20") (pintype "bidirectional"))
      (node (ref "IC8") (pin "5") (pinfunction "VOUT_5") (pintype "bidirectional"))
    )
    (net (code "45") (name "Net-(IC9-ALERT|BUSY)") (class "Default")
      (node (ref "IC9") (pin "P$17") (pinfunction "ALERT|BUSY_P$17") (pintype "bidirectional"))
      (node (ref "R12") (pin "2") (pinfunction "2_2") (pintype "passive"))
    )
    (net (code "46") (name "Net-(IC9-VIN_6)") (class "Default")
      (node (ref "IC9") (pin "P$12") (pinfunction "VIN_6_P$12") (pintype "bidirectional"))
      (node (ref "R33") (pin "1") (pinfunction "1_1") (pintype "passive"))
      (node (ref "R34") (pin "2") (pinfunction "2_2") (pintype "passive"))
    )
    (net (code "47") (name "Net-(IC9-VIN_8)") (class "Default")
      (node (ref "IC9") (pin "P$11") (pinfunction "VIN_8_P$11") (pintype "bidirectional"))
      (node (ref "R35") (pin "1") (pinfunction "1_1") (pintype "passive"))
      (node (ref "R36") (pin "2") (pinfunction "2_2") (pintype "passive"))
    )
    (net (code "48") (name "Net-(IC10-CIN1)") (class "Default")
      (node (ref "IC10") (pin "P$3") (pinfunction "CIN1_P$3") (pintype "bidirectional"))
      (node (ref "R30") (pin "1") (pinfunction "1_1") (pintype "passive"))
      (node (ref "R31") (pin "2") (pinfunction "2_2") (pintype "passive"))
    )
    (net (code "49") (name "Net-(IC10-CIN2)") (class "Default")
      (node (ref "IC10") (pin "P$4") (pinfunction "CIN2_P$4") (pintype "bidirectional"))
      (node (ref "R29") (pin "1") (pinfunction "1_1") (pintype "passive"))
      (node (ref "R32") (pin "2") (pinfunction "2_2") (pintype "passive"))
    )
    (net (code "50") (name "Net-(IC10-COT1)") (class "Default")
      (node (ref "H1") (pin "50") (pinfunction "50_50") (pintype "bidirectional"))
      (node (ref "IC10") (pin "P$8") (pinfunction "COT1_P$8") (pintype "bidirectional"))
      (node (ref "R38") (pin "1") (pinfunction "1_1") (pintype "passive"))
    )
    (net (code "51") (name "Net-(IC10-COT2)") (class "Default")
      (node (ref "IC10") (pin "P$7") (pinfunction "COT2_P$7") (pintype "bidirectional"))
      (node (ref "Q4") (pin "P$4-G") (pinfunction "G_P$4-G") (pintype "passive"))
      (node (ref "R39") (pin "1") (pinfunction "1_1") (pintype "passive"))
    )
    (net (code "52") (name "Net-(IC10-OUT)") (class "Default")
      (node (ref "IC10") (pin "P$2") (pinfunction "OUT_P$2") (pintype "bidirectional"))
      (node (ref "R29") (pin "2") (pinfunction "2_2") (pintype "passive"))
      (node (ref "R30") (pin "2") (pinfunction "2_2") (pintype "passive"))
    )
    (net (code "53") (name "Net-(IC10-RS+)") (class "Default")
      (node (ref "C4") (pin "+") (pinfunction "+_+") (pintype "passive"))
      (node (ref "D1") (pin "P$1-CATHODE") (pinfunction "P$1-CATHODE_P$1-CATHODE") (pintype "bidirectional"))
      (node (ref "IC10") (pin "P$10") (pinfunction "RS+_P$10") (pintype "bidirectional"))
      (node (ref "R1") (pin "2") (pinfunction "2_2") (pintype "passive"))
      (node (ref "R37") (pin "2") (pinfunction "2_2") (pintype "passive"))
    )
    (net (code "54") (name "Net-(IC10-RS-)") (class "Default")
      (node (ref "C15") (pin "1") (pinfunction "1_1") (pintype "passive"))
      (node (ref "C16") (pin "1") (pinfunction "1_1") (pintype "passive"))
      (node (ref "H1") (pin "26") (pinfunction "26_26") (pintype "bidirectional"))
      (node (ref "H1") (pin "28") (pinfunction "28_28") (pintype "bidirectional"))
      (node (ref "IC10") (pin "P$9") (pinfunction "RS-_P$9") (pintype "bidirectional"))
      (node (ref "IC6") (pin "2") (pinfunction "VCC_2") (pintype "bidirectional"))
      (node (ref "IC7") (pin "2") (pinfunction "VCC_2") (pintype "bidirectional"))
      (node (ref "IC8") (pin "1") (pinfunction "VIN_1") (pintype "bidirectional"))
      (node (ref "R11") (pin "2") (pinfunction "2_2") (pintype "passive"))
      (node (ref "R2") (pin "2") (pinfunction "2_2") (pintype "passive"))
      (node (ref "R25") (pin "2") (pinfunction "2_2") (pintype "passive"))
      (node (ref "R26") (pin "2") (pinfunction "2_2") (pintype "passive"))
      (node (ref "R28") (pin "2") (pinfunction "2_2") (pintype "passive"))
      (node (ref "R3") (pin "2") (pinfunction "2_2") (pintype "passive"))
      (node (ref "R37") (pin "1") (pinfunction "1_1") (pintype "passive"))
    )
    (net (code "55") (name "Net-(IC10-VCC)") (class "Default")
      (node (ref "IC10") (pin "P$1") (pinfunction "VCC_P$1") (pintype "bidirectional"))
      (node (ref "IC11") (pin "5") (pinfunction "VOUT_5") (pintype "bidirectional"))
    )
    (net (code "56") (name "Net-(Q6-G)") (class "Default")
      (node (ref "H1") (pin "38") (pinfunction "38_38") (pintype "bidirectional"))
      (node (ref "Q6") (pin "P$4-G") (pinfunction "G_P$4-G") (pintype "passive"))
      (node (ref "R24") (pin "1") (pinfunction "1_1") (pintype "passive"))
    )
    (net (code "57") (name "Net-(Q8-G)") (class "Default")
      (node (ref "H1") (pin "36") (pinfunction "36_36") (pintype "bidirectional"))
      (node (ref "Q8") (pin "P$4-G") (pinfunction "G_P$4-G") (pintype "passive"))
      (node (ref "R6") (pin "1") (pinfunction "1_1") (pintype "passive"))
    )
    (net (code "58") (name "unconnected-(H1-Pad5)") (class "Default")
      (node (ref "H1") (pin "5") (pinfunction "5_5") (pintype "bidirectional"))
    )
    (net (code "59") (name "unconnected-(H1-Pad7)") (class "Default")
      (node (ref "H1") (pin "7") (pinfunction "7_7") (pintype "bidirectional"))
    )
    (net (code "60") (name "unconnected-(H1-Pad9)") (class "Default")
      (node (ref "H1") (pin "9") (pinfunction "9_9") (pintype "bidirectional"))
    )
    (net (code "61") (name "unconnected-(H1-Pad11)") (class "Default")
      (node (ref "H1") (pin "11") (pinfunction "11_11") (pintype "bidirectional"))
    )
    (net (code "62") (name "unconnected-(H1-Pad13)") (class "Default")
      (node (ref "H1") (pin "13") (pinfunction "13_13") (pintype "bidirectional"))
    )
    (net (code "63") (name "unconnected-(H1-Pad14)") (class "Default")
      (node (ref "H1") (pin "14") (pinfunction "14_14") (pintype "bidirectional"))
    )
    (net (code "64") (name "unconnected-(H1-Pad15)") (class "Default")
      (node (ref "H1") (pin "15") (pinfunction "15_15") (pintype "bidirectional"))
    )
    (net (code "65") (name "unconnected-(H1-Pad17)") (class "Default")
      (node (ref "H1") (pin "17") (pinfunction "17_17") (pintype "bidirectional"))
    )
    (net (code "66") (name "unconnected-(H1-Pad18)") (class "Default")
      (node (ref "H1") (pin "18") (pinfunction "18_18") (pintype "bidirectional"))
    )
    (net (code "67") (name "unconnected-(H1-Pad19)") (class "Default")
      (node (ref "H1") (pin "19") (pinfunction "19_19") (pintype "bidirectional"))
    )
    (net (code "68") (name "unconnected-(H1-Pad21)") (class "Default")
      (node (ref "H1") (pin "21") (pinfunction "21_21") (pintype "bidirectional"))
    )
    (net (code "69") (name "unconnected-(H1-Pad23)") (class "Default")
      (node (ref "H1") (pin "23") (pinfunction "23_23") (pintype "bidirectional"))
    )
    (net (code "70") (name "unconnected-(H1-Pad25)") (class "Default")
      (node (ref "H1") (pin "25") (pinfunction "25_25") (pintype "bidirectional"))
    )
    (net (code "71") (name "unconnected-(H1-Pad27)") (class "Default")
      (node (ref "H1") (pin "27") (pinfunction "27_27") (pintype "bidirectional"))
    )
    (net (code "72") (name "unconnected-(H1-Pad32)") (class "Default")
      (node (ref "H1") (pin "32") (pinfunction "32_32") (pintype "bidirectional"))
    )
    (net (code "73") (name "unconnected-(H1-Pad34)") (class "Default")
      (node (ref "H1") (pin "34") (pinfunction "34_34") (pintype "bidirectional"))
    )
    (net (code "74") (name "unconnected-(H1-Pad39)") (class "Default")
      (node (ref "H1") (pin "39") (pinfunction "39_39") (pintype "bidirectional"))
    )
    (net (code "75") (name "unconnected-(H1-Pad42)") (class "Default")
      (node (ref "H1") (pin "42") (pinfunction "42_42") (pintype "bidirectional"))
    )
    (net (code "76") (name "unconnected-(H1-Pad43)") (class "Default")
      (node (ref "H1") (pin "43") (pinfunction "43_43") (pintype "bidirectional"))
    )
    (net (code "77") (name "unconnected-(H1-Pad44)") (class "Default")
      (node (ref "H1") (pin "44") (pinfunction "44_44") (pintype "bidirectional"))
    )
    (net (code "78") (name "unconnected-(H1-Pad46)") (class "Default")
      (node (ref "H1") (pin "46") (pinfunction "46_46") (pintype "bidirectional"))
    )
    (net (code "79") (name "unconnected-(H1-Pad47)") (class "Default")
      (node (ref "H1") (pin "47") (pinfunction "47_47") (pintype "bidirectional"))
    )
    (net (code "80") (name "unconnected-(H1-Pad48)") (class "Default")
      (node (ref "H1") (pin "48") (pinfunction "48_48") (pintype "bidirectional"))
    )
    (net (code "81") (name "unconnected-(H1-Pad51)") (class "Default")
      (node (ref "H1") (pin "51") (pinfunction "51_51") (pintype "bidirectional"))
    )
    (net (code "82") (name "unconnected-(H1-Pad52)") (class "Default")
      (node (ref "H1") (pin "52") (pinfunction "52_52") (pintype "bidirectional"))
    )
    (net (code "83") (name "unconnected-(H2-Pad1)") (class "Default")
      (node (ref "H2") (pin "1") (pinfunction "1_1") (pintype "bidirectional"))
    )
    (net (code "84") (name "unconnected-(H2-Pad2)") (class "Default")
      (node (ref "H2") (pin "2") (pinfunction "2_2") (pintype "bidirectional"))
    )
    (net (code "85") (name "unconnected-(H2-Pad3)") (class "Default")
      (node (ref "H2") (pin "3") (pinfunction "3_3") (pintype "bidirectional"))
    )
    (net (code "86") (name "unconnected-(H2-Pad4)") (class "Default")
      (node (ref "H2") (pin "4") (pinfunction "4_4") (pintype "bidirectional"))
    )
    (net (code "87") (name "unconnected-(H2-Pad5)") (class "Default")
      (node (ref "H2") (pin "5") (pinfunction "5_5") (pintype "bidirectional"))
    )
    (net (code "88") (name "unconnected-(H2-Pad6)") (class "Default")
      (node (ref "H2") (pin "6") (pinfunction "6_6") (pintype "bidirectional"))
    )
    (net (code "89") (name "unconnected-(H2-Pad7)") (class "Default")
      (node (ref "H2") (pin "7") (pinfunction "7_7") (pintype "bidirectional"))
    )
    (net (code "90") (name "unconnected-(H2-Pad8)") (class "Default")
      (node (ref "H2") (pin "8") (pinfunction "8_8") (pintype "bidirectional"))
    )
    (net (code "91") (name "unconnected-(H2-Pad9)") (class "Default")
      (node (ref "H2") (pin "9") (pinfunction "9_9") (pintype "bidirectional"))
    )
    (net (code "92") (name "unconnected-(H2-Pad10)") (class "Default")
      (node (ref "H2") (pin "10") (pinfunction "10_10") (pintype "bidirectional"))
    )
    (net (code "93") (name "unconnected-(H2-Pad11)") (class "Default")
      (node (ref "H2") (pin "11") (pinfunction "11_11") (pintype "bidirectional"))
    )
    (net (code "94") (name "unconnected-(H2-Pad12)") (class "Default")
      (node (ref "H2") (pin "12") (pinfunction "12_12") (pintype "bidirectional"))
    )
    (net (code "95") (name "unconnected-(H2-Pad13)") (class "Default")
      (node (ref "H2") (pin "13") (pinfunction "13_13") (pintype "bidirectional"))
    )
    (net (code "96") (name "unconnected-(H2-Pad14)") (class "Default")
      (node (ref "H2") (pin "14") (pinfunction "14_14") (pintype "bidirectional"))
    )
    (net (code "97") (name "unconnected-(H2-Pad15)") (class "Default")
      (node (ref "H2") (pin "15") (pinfunction "15_15") (pintype "bidirectional"))
    )
    (net (code "98") (name "unconnected-(H2-Pad16)") (class "Default")
      (node (ref "H2") (pin "16") (pinfunction "16_16") (pintype "bidirectional"))
    )
    (net (code "99") (name "unconnected-(H2-Pad21)") (class "Default")
      (node (ref "H2") (pin "21") (pinfunction "21_21") (pintype "bidirectional"))
    )
    (net (code "100") (name "unconnected-(H2-Pad22)") (class "Default")
      (node (ref "H2") (pin "22") (pinfunction "22_22") (pintype "bidirectional"))
    )
    (net (code "101") (name "unconnected-(H2-Pad23)") (class "Default")
      (node (ref "H2") (pin "23") (pinfunction "23_23") (pintype "bidirectional"))
    )
    (net (code "102") (name "unconnected-(H2-Pad24)") (class "Default")
      (node (ref "H2") (pin "24") (pinfunction "24_24") (pintype "bidirectional"))
    )
    (net (code "103") (name "unconnected-(H2-Pad25)") (class "Default")
      (node (ref "H2") (pin "25") (pinfunction "25_25") (pintype "bidirectional"))
    )
    (net (code "104") (name "unconnected-(H2-Pad26)") (class "Default")
      (node (ref "H2") (pin "26") (pinfunction "26_26") (pintype "bidirectional"))
    )
    (net (code "105") (name "unconnected-(H2-Pad27)") (class "Default")
      (node (ref "H2") (pin "27") (pinfunction "27_27") (pintype "bidirectional"))
    )
    (net (code "106") (name "unconnected-(H2-Pad28)") (class "Default")
      (node (ref "H2") (pin "28") (pinfunction "28_28") (pintype "bidirectional"))
    )
    (net (code "107") (name "unconnected-(H2-Pad29)") (class "Default")
      (node (ref "H2") (pin "29") (pinfunction "29_29") (pintype "bidirectional"))
    )
    (net (code "108") (name "unconnected-(H2-Pad30)") (class "Default")
      (node (ref "H2") (pin "30") (pinfunction "30_30") (pintype "bidirectional"))
    )
    (net (code "109") (name "unconnected-(H2-Pad32)") (class "Default")
      (node (ref "H2") (pin "32") (pinfunction "32_32") (pintype "bidirectional"))
    )
    (net (code "110") (name "unconnected-(H2-Pad34)") (class "Default")
      (node (ref "H2") (pin "34") (pinfunction "34_34") (pintype "bidirectional"))
    )
    (net (code "111") (name "unconnected-(H2-Pad35)") (class "Default")
      (node (ref "H2") (pin "35") (pinfunction "35_35") (pintype "bidirectional"))
    )
    (net (code "112") (name "unconnected-(H2-Pad37)") (class "Default")
      (node (ref "H2") (pin "37") (pinfunction "37_37") (pintype "bidirectional"))
    )
    (net (code "113") (name "unconnected-(H2-Pad38)") (class "Default")
      (node (ref "H2") (pin "38") (pinfunction "38_38") (pintype "bidirectional"))
    )
    (net (code "114") (name "unconnected-(H2-Pad39)") (class "Default")
      (node (ref "H2") (pin "39") (pinfunction "39_39") (pintype "bidirectional"))
    )
    (net (code "115") (name "unconnected-(H2-Pad40)") (class "Default")
      (node (ref "H2") (pin "40") (pinfunction "40_40") (pintype "bidirectional"))
    )
    (net (code "116") (name "unconnected-(H2-Pad41)") (class "Default")
      (node (ref "H2") (pin "41") (pinfunction "41_41") (pintype "bidirectional"))
    )
    (net (code "117") (name "unconnected-(H2-Pad42)") (class "Default")
      (node (ref "H2") (pin "42") (pinfunction "42_42") (pintype "bidirectional"))
    )
    (net (code "118") (name "unconnected-(H2-Pad43)") (class "Default")
      (node (ref "H2") (pin "43") (pinfunction "43_43") (pintype "bidirectional"))
    )
    (net (code "119") (name "unconnected-(H2-Pad44)") (class "Default")
      (node (ref "H2") (pin "44") (pinfunction "44_44") (pintype "bidirectional"))
    )
    (net (code "120") (name "unconnected-(H2-Pad45)") (class "Default")
      (node (ref "H2") (pin "45") (pinfunction "45_45") (pintype "bidirectional"))
    )
    (net (code "121") (name "unconnected-(H2-Pad46)") (class "Default")
      (node (ref "H2") (pin "46") (pinfunction "46_46") (pintype "bidirectional"))
    )
    (net (code "122") (name "unconnected-(H2-Pad47)") (class "Default")
      (node (ref "H2") (pin "47") (pinfunction "47_47") (pintype "bidirectional"))
    )
    (net (code "123") (name "unconnected-(H2-Pad48)") (class "Default")
      (node (ref "H2") (pin "48") (pinfunction "48_48") (pintype "bidirectional"))
    )
    (net (code "124") (name "unconnected-(H2-Pad49)") (class "Default")
      (node (ref "H2") (pin "49") (pinfunction "49_49") (pintype "bidirectional"))
    )
    (net (code "125") (name "unconnected-(H2-Pad50)") (class "Default")
      (node (ref "H2") (pin "50") (pinfunction "50_50") (pintype "bidirectional"))
    )
    (net (code "126") (name "unconnected-(IC8-N{slash}C-Pad4)") (class "Default")
      (node (ref "IC8") (pin "4") (pinfunction "N/C_4") (pintype "bidirectional"))
    )
    (net (code "127") (name "unconnected-(IC11-N{slash}C-Pad4)") (class "Default")
      (node (ref "IC11") (pin "4") (pinfunction "N/C_4") (pintype "bidirectional"))
    )
    (net (code "128") (name "unconnected-(U$1-PadP$1)") (class "Default")
      (node (ref "U$1") (pin "P$1") (pinfunction "P$1_P$1") (pintype "bidirectional"))
    )
  )
)
